# main.net
KiCad netlist of a schematic drawn in EAGLE
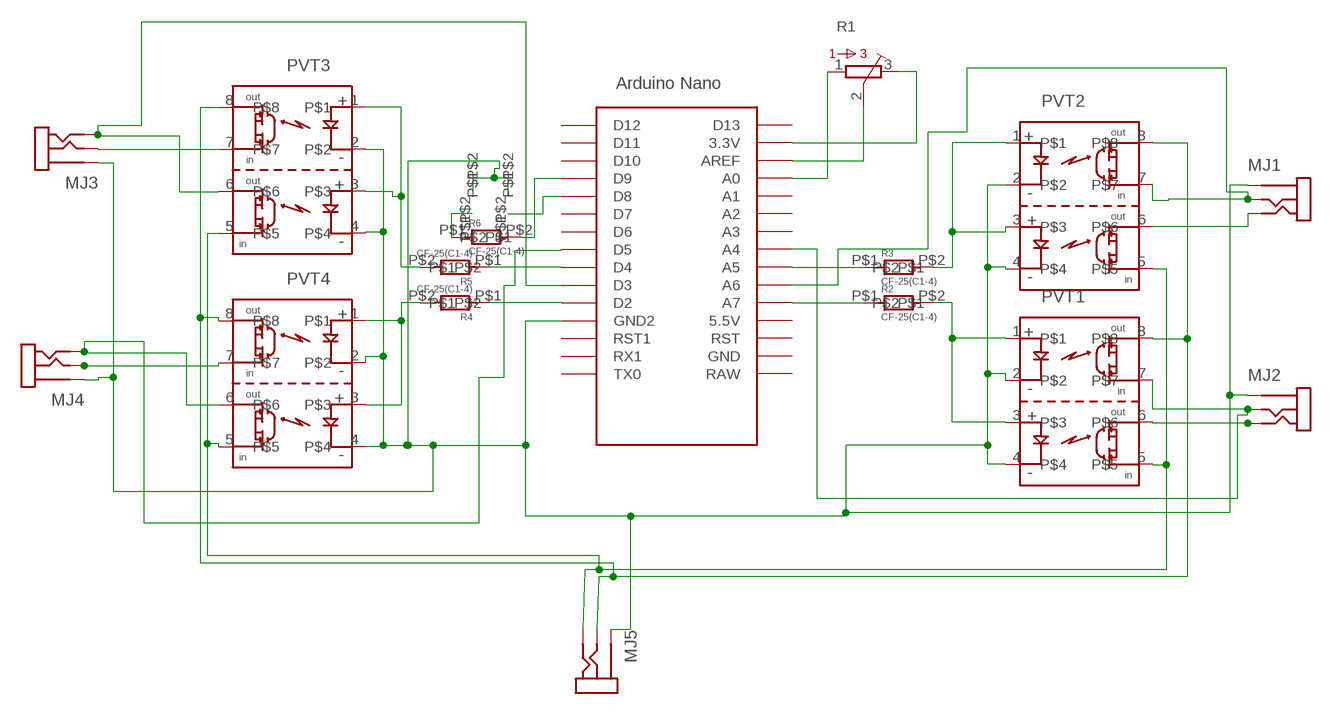
[diagram p0: schematic, sheet 1]

(export (version "E")
  (design (tool "Eeschema 10.0.6"))
  (components
    (comp (ref "MJ1")
      (value "MINIJACKF")
      (footprint "eagle-import:MINIJACKF")
      (libsource (lib "eagle-import") (part "MINIJACKF"))
    )
    (comp (ref "MJ2")
      (value "MINIJACKF")
      (footprint "eagle-import:MINIJACKF")
      (libsource (lib "eagle-import") (part "MINIJACKF"))
    )
    (comp (ref "MJ3")
      (value "MINIJACKF")
      (footprint "eagle-import:MINIJACKF")
      (libsource (lib "eagle-import") (part "MINIJACKF"))
    )
    (comp (ref "MJ4")
      (value "MINIJACKF")
      (footprint "eagle-import:MINIJACKF")
      (libsource (lib "eagle-import") (part "MINIJACKF"))
    )
    (comp (ref "MJ5")
      (value "MINIJACKF")
      (footprint "eagle-import:MINIJACKF")
      (libsource (lib "eagle-import") (part "MINIJACKF"))
    )
    (comp (ref "PVT1")
      (value "PVT322A")
      (footprint "eagle-import:DIP-8")
      (libsource (lib "eagle-import") (part "PVT322A"))
    )
    (comp (ref "PVT2")
      (value "PVT322A")
      (footprint "eagle-import:DIP-8")
      (libsource (lib "eagle-import") (part "PVT322A"))
    )
    (comp (ref "PVT3")
      (value "PVT322A")
      (footprint "eagle-import:DIP-8")
      (libsource (lib "eagle-import") (part "PVT322A"))
    )
    (comp (ref "PVT4")
      (value "PVT322A")
      (footprint "eagle-import:DIP-8")
      (libsource (lib "eagle-import") (part "PVT322A"))
    )
    (comp (ref "R1")
      (value "3362H")
      (footprint "eagle-import:3362H")
      (libsource (lib "eagle-import") (part "3362H"))
    )
    (comp (ref "R2")
      (value "CF-25(C1-4)")
      (footprint "eagle-import:CF-25(C1-4)")
      (libsource (lib "eagle-import") (part "CF-25(C1-4)"))
    )
    (comp (ref "R3")
      (value "CF-25(C1-4)")
      (footprint "eagle-import:CF-25(C1-4)")
      (libsource (lib "eagle-import") (part "CF-25(C1-4)"))
    )
    (comp (ref "R4")
      (value "CF-25(C1-4)")
      (footprint "eagle-import:CF-25(C1-4)")
      (libsource (lib "eagle-import") (part "CF-25(C1-4)"))
    )
    (comp (ref "R5")
      (value "CF-25(C1-4)")
      (footprint "eagle-import:CF-25(C1-4)")
      (libsource (lib "eagle-import") (part "CF-25(C1-4)"))
    )
    (comp (ref "R6")
      (value "CF-25(C1-4)")
      (footprint "eagle-import:CF-25(C1-4)")
      (libsource (lib "eagle-import") (part "resistance_10621108_CF-25(C1-4)"))
    )
    (comp (ref "U$1")
      (value "NANO")
      (footprint "eagle-import:NANO")
      (libsource (lib "eagle-import") (part "NANO"))
    )
    (comp (ref "U$2")
      (value "2PINCONNECTOR")
      (footprint "eagle-import:2PIN")
      (libsource (lib "eagle-import") (part "2PINCONNECTOR"))
    )
    (comp (ref "U$3")
      (value "2PINCONNECTOR")
      (footprint "eagle-import:2PIN")
      (libsource (lib "eagle-import") (part "2PINCONNECTOR"))
    )
  )
  (nets
    (net (code "1") (name "Net-(MJ1-P$1)") (class "Default")
      (node (ref "MJ1") (pin "GND") (pinfunction "P$1_GND") (pintype "bidirectional"))
      (node (ref "MJ2") (pin "GND") (pinfunction "P$1_GND") (pintype "bidirectional"))
      (node (ref "MJ3") (pin "GND") (pinfunction "P$1_GND") (pintype "bidirectional"))
      (node (ref "MJ4") (pin "GND") (pinfunction "P$1_GND") (pintype "bidirectional"))
      (node (ref "MJ5") (pin "GND") (pinfunction "P$1_GND") (pintype "bidirectional"))
      (node (ref "PVT1") (pin "2") (pinfunction "P$2_2") (pintype "bidirectional"))
      (node (ref "PVT1") (pin "4") (pinfunction "P$4_4") (pintype "bidirectional"))
      (node (ref "PVT2") (pin "2") (pinfunction "P$2_2") (pintype "bidirectional"))
      (node (ref "PVT2") (pin "4") (pinfunction "P$4_4") (pintype "bidirectional"))
      (node (ref "PVT3") (pin "2") (pinfunction "P$2_2") (pintype "bidirectional"))
      (node (ref "PVT3") (pin "4") (pinfunction "P$4_4") (pintype "bidirectional"))
      (node (ref "PVT4") (pin "2") (pinfunction "P$2_2") (pintype "bidirectional"))
      (node (ref "PVT4") (pin "4") (pinfunction "P$4_4") (pintype "bidirectional"))
      (node (ref "U$1") (pin "GND1") (pinfunction "GND2_GND1") (pintype "bidirectional"))
      (node (ref "U$2") (pin "P$2") (pinfunction "P$2_P$2") (pintype "bidirectional"))
      (node (ref "U$3") (pin "P$2") (pinfunction "P$2_P$2") (pintype "bidirectional"))
    )
    (net (code "2") (name "Net-(MJ1-P$2)") (class "Default")
      (node (ref "MJ1") (pin "LEFT") (pinfunction "P$2_LEFT") (pintype "bidirectional"))
      (node (ref "PVT2") (pin "7") (pinfunction "P$7_7") (pintype "bidirectional"))
      (node (ref "U$1") (pin "A6") (pinfunction "A6_A6") (pintype "bidirectional"))
    )
    (net (code "3") (name "Net-(MJ1-P$3)") (class "Default")
      (node (ref "MJ1") (pin "RIGHT") (pinfunction "P$3_RIGHT") (pintype "bidirectional"))
      (node (ref "PVT2") (pin "6") (pinfunction "P$6_6") (pintype "bidirectional"))
    )
    (net (code "4") (name "Net-(MJ2-P$2)") (class "Default")
      (node (ref "MJ2") (pin "LEFT") (pinfunction "P$2_LEFT") (pintype "bidirectional"))
      (node (ref "PVT1") (pin "7") (pinfunction "P$7_7") (pintype "bidirectional"))
      (node (ref "U$1") (pin "A4") (pinfunction "A4_A4") (pintype "bidirectional"))
    )
    (net (code "5") (name "Net-(MJ2-P$3)") (class "Default")
      (node (ref "MJ2") (pin "RIGHT") (pinfunction "P$3_RIGHT") (pintype "bidirectional"))
      (node (ref "PVT1") (pin "6") (pinfunction "P$6_6") (pintype "bidirectional"))
    )
    (net (code "6") (name "Net-(MJ3-P$2)") (class "Default")
      (node (ref "MJ3") (pin "LEFT") (pinfunction "P$2_LEFT") (pintype "bidirectional"))
      (node (ref "PVT3") (pin "7") (pinfunction "P$7_7") (pintype "bidirectional"))
    )
    (net (code "7") (name "Net-(MJ3-P$3)") (class "Default")
      (node (ref "MJ3") (pin "RIGHT") (pinfunction "P$3_RIGHT") (pintype "bidirectional"))
      (node (ref "PVT3") (pin "6") (pinfunction "P$6_6") (pintype "bidirectional"))
      (node (ref "U$1") (pin "D3") (pinfunction "D3_D3") (pintype "bidirectional"))
    )
    (net (code "8") (name "Net-(MJ4-P$2)") (class "Default")
      (node (ref "MJ4") (pin "LEFT") (pinfunction "P$2_LEFT") (pintype "bidirectional"))
      (node (ref "PVT4") (pin "7") (pinfunction "P$7_7") (pintype "bidirectional"))
    )
    (net (code "9") (name "Net-(MJ4-P$3)") (class "Default")
      (node (ref "MJ4") (pin "RIGHT") (pinfunction "P$3_RIGHT") (pintype "bidirectional"))
      (node (ref "PVT4") (pin "6") (pinfunction "P$6_6") (pintype "bidirectional"))
      (node (ref "U$1") (pin "D5") (pinfunction "D5_D5") (pintype "bidirectional"))
    )
    (net (code "10") (name "Net-(MJ5-P$2)") (class "Default")
      (node (ref "MJ5") (pin "LEFT") (pinfunction "P$2_LEFT") (pintype "bidirectional"))
      (node (ref "PVT1") (pin "8") (pinfunction "P$8_8") (pintype "bidirectional"))
      (node (ref "PVT2") (pin "8") (pinfunction "P$8_8") (pintype "bidirectional"))
      (node (ref "PVT3") (pin "8") (pinfunction "P$8_8") (pintype "bidirectional"))
      (node (ref "PVT4") (pin "8") (pinfunction "P$8_8") (pintype "bidirectional"))
    )
    (net (code "11") (name "Net-(MJ5-P$3)") (class "Default")
      (node (ref "MJ5") (pin "RIGHT") (pinfunction "P$3_RIGHT") (pintype "bidirectional"))
      (node (ref "PVT1") (pin "5") (pinfunction "P$5_5") (pintype "bidirectional"))
      (node (ref "PVT2") (pin "5") (pinfunction "P$5_5") (pintype "bidirectional"))
      (node (ref "PVT3") (pin "5") (pinfunction "P$5_5") (pintype "bidirectional"))
      (node (ref "PVT4") (pin "5") (pinfunction "P$5_5") (pintype "bidirectional"))
    )
    (net (code "12") (name "Net-(PVT1-P$1)") (class "Default")
      (node (ref "PVT1") (pin "1") (pinfunction "P$1_1") (pintype "bidirectional"))
      (node (ref "PVT1") (pin "3") (pinfunction "P$3_3") (pintype "bidirectional"))
      (node (ref "R2") (pin "P$2") (pinfunction "P$2_P$2") (pintype "bidirectional"))
    )
    (net (code "13") (name "Net-(PVT2-P$1)") (class "Default")
      (node (ref "PVT2") (pin "1") (pinfunction "P$1_1") (pintype "bidirectional"))
      (node (ref "PVT2") (pin "3") (pinfunction "P$3_3") (pintype "bidirectional"))
      (node (ref "R3") (pin "P$2") (pinfunction "P$2_P$2") (pintype "bidirectional"))
    )
    (net (code "14") (name "Net-(PVT3-P$1)") (class "Default")
      (node (ref "PVT3") (pin "1") (pinfunction "P$1_1") (pintype "bidirectional"))
      (node (ref "PVT3") (pin "3") (pinfunction "P$3_3") (pintype "bidirectional"))
      (node (ref "R5") (pin "P$2") (pinfunction "P$2_P$2") (pintype "bidirectional"))
    )
    (net (code "15") (name "Net-(PVT4-P$1)") (class "Default")
      (node (ref "PVT4") (pin "1") (pinfunction "P$1_1") (pintype "bidirectional"))
      (node (ref "PVT4") (pin "3") (pinfunction "P$3_3") (pintype "bidirectional"))
      (node (ref "R4") (pin "P$2") (pinfunction "P$2_P$2") (pintype "bidirectional"))
    )
    (net (code "16") (name "Net-(R1-Pad1)") (class "Default")
      (node (ref "R1") (pin "1") (pinfunction "1_1") (pintype "passive"))
      (node (ref "U$1") (pin "A0") (pinfunction "A0_A0") (pintype "bidirectional"))
    )
    (net (code "17") (name "Net-(R1-Pad2)") (class "Default")
      (node (ref "R1") (pin "2") (pinfunction "2_2") (pintype "passive"))
      (node (ref "U$1") (pin "AREF") (pinfunction "AREF_AREF") (pintype "bidirectional"))
    )
    (net (code "18") (name "Net-(R1-Pad3)") (class "Default")
      (node (ref "R1") (pin "3") (pinfunction "3_3") (pintype "passive"))
      (node (ref "U$1") (pin "3.3V") (pinfunction "3.3V_3.3V") (pintype "bidirectional"))
    )
    (net (code "19") (name "Net-(R2-PadP$1)") (class "Default")
      (node (ref "R2") (pin "P$1") (pinfunction "P$1_P$1") (pintype "bidirectional"))
      (node (ref "U$1") (pin "A7") (pinfunction "A7_A7") (pintype "bidirectional"))
    )
    (net (code "20") (name "Net-(R3-PadP$1)") (class "Default")
      (node (ref "R3") (pin "P$1") (pinfunction "P$1_P$1") (pintype "bidirectional"))
      (node (ref "U$1") (pin "A5") (pinfunction "A5_A5") (pintype "bidirectional"))
    )
    (net (code "21") (name "Net-(R4-PadP$1)") (class "Default")
      (node (ref "R4") (pin "P$1") (pinfunction "P$1_P$1") (pintype "bidirectional"))
      (node (ref "U$1") (pin "D2") (pinfunction "D2_D2") (pintype "bidirectional"))
    )
    (net (code "22") (name "Net-(R5-PadP$1)") (class "Default")
      (node (ref "R5") (pin "P$1") (pinfunction "P$1_P$1") (pintype "bidirectional"))
      (node (ref "U$1") (pin "D4") (pinfunction "D4_D4") (pintype "bidirectional"))
    )
    (net (code "23") (name "Net-(R6-PadP$1)") (class "Default")
      (node (ref "R6") (pin "P$1") (pinfunction "P$1_P$1") (pintype "bidirectional"))
      (node (ref "U$3") (pin "P$1") (pinfunction "P$1_P$1") (pintype "bidirectional"))
    )
    (net (code "24") (name "Net-(R6-PadP$2)") (class "Default")
      (node (ref "R6") (pin "P$2") (pinfunction "P$2_P$2") (pintype "bidirectional"))
      (node (ref "U$1") (pin "D9") (pinfunction "D9_D9") (pintype "bidirectional"))
    )
    (net (code "25") (name "Net-(U$1-PadD8)") (class "Default")
      (node (ref "U$1") (pin "D8") (pinfunction "D8_D8") (pintype "bidirectional"))
      (node (ref "U$2") (pin "P$1") (pinfunction "P$1_P$1") (pintype "bidirectional"))
    )
    (net (code "26") (name "unconnected-(U$1-5.5V-Pad5V)") (class "Default")
      (node (ref "U$1") (pin "5V") (pinfunction "5.5V_5V") (pintype "bidirectional"))
    )
    (net (code "27") (name "unconnected-(U$1-PadA1)") (class "Default")
      (node (ref "U$1") (pin "A1") (pinfunction "A1_A1") (pintype "bidirectional"))
    )
    (net (code "28") (name "unconnected-(U$1-PadA2)") (class "Default")
      (node (ref "U$1") (pin "A2") (pinfunction "A2_A2") (pintype "bidirectional"))
    )
    (net (code "29") (name "unconnected-(U$1-PadA3)") (class "Default")
      (node (ref "U$1") (pin "A3") (pinfunction "A3_A3") (pintype "bidirectional"))
    )
    (net (code "30") (name "unconnected-(U$1-PadD6)") (class "Default")
      (node (ref "U$1") (pin "D6") (pinfunction "D6_D6") (pintype "bidirectional"))
    )
    (net (code "31") (name "unconnected-(U$1-PadD7)") (class "Default")
      (node (ref "U$1") (pin "D7") (pinfunction "D7_D7") (pintype "bidirectional"))
    )
    (net (code "32") (name "unconnected-(U$1-PadD10)") (class "Default")
      (node (ref "U$1") (pin "D10") (pinfunction "D10_D10") (pintype "bidirectional"))
    )
    (net (code "33") (name "unconnected-(U$1-PadD11)") (class "Default")
      (node (ref "U$1") (pin "D11") (pinfunction "D11_D11") (pintype "bidirectional"))
    )
    (net (code "34") (name "unconnected-(U$1-PadD12)") (class "Default")
      (node (ref "U$1") (pin "D12") (pinfunction "D12_D12") (pintype "bidirectional"))
    )
    (net (code "35") (name "unconnected-(U$1-PadD13)") (class "Default")
      (node (ref "U$1") (pin "D13") (pinfunction "D13_D13") (pintype "bidirectional"))
    )
    (net (code "36") (name "unconnected-(U$1-PadGND)") (class "Default")
      (node (ref "U$1") (pin "GND") (pinfunction "GND_GND") (pintype "bidirectional"))
    )
    (net (code "37") (name "unconnected-(U$1-PadRAW)") (class "Default")
      (node (ref "U$1") (pin "RAW") (pinfunction "RAW_RAW") (pintype "bidirectional"))
    )
    (net (code "38") (name "unconnected-(U$1-PadRST)") (class "Default")
      (node (ref "U$1") (pin "RST") (pinfunction "RST_RST") (pintype "bidirectional"))
    )
    (net (code "39") (name "unconnected-(U$1-PadRST1)") (class "Default")
      (node (ref "U$1") (pin "RST1") (pinfunction "RST1_RST1") (pintype "bidirectional"))
    )
    (net (code "40") (name "unconnected-(U$1-PadRX1)") (class "Default")
      (node (ref "U$1") (pin "RX1") (pinfunction "RX1_RX1") (pintype "bidirectional"))
    )
    (net (code "41") (name "unconnected-(U$1-PadTX0)") (class "Default")
      (node (ref "U$1") (pin "TX0") (pinfunction "TX0_TX0") (pintype "bidirectional"))
    )
  )
)
